# Timer_Sheet.net
KiCad netlist of a schematic drawn in Altium Designer
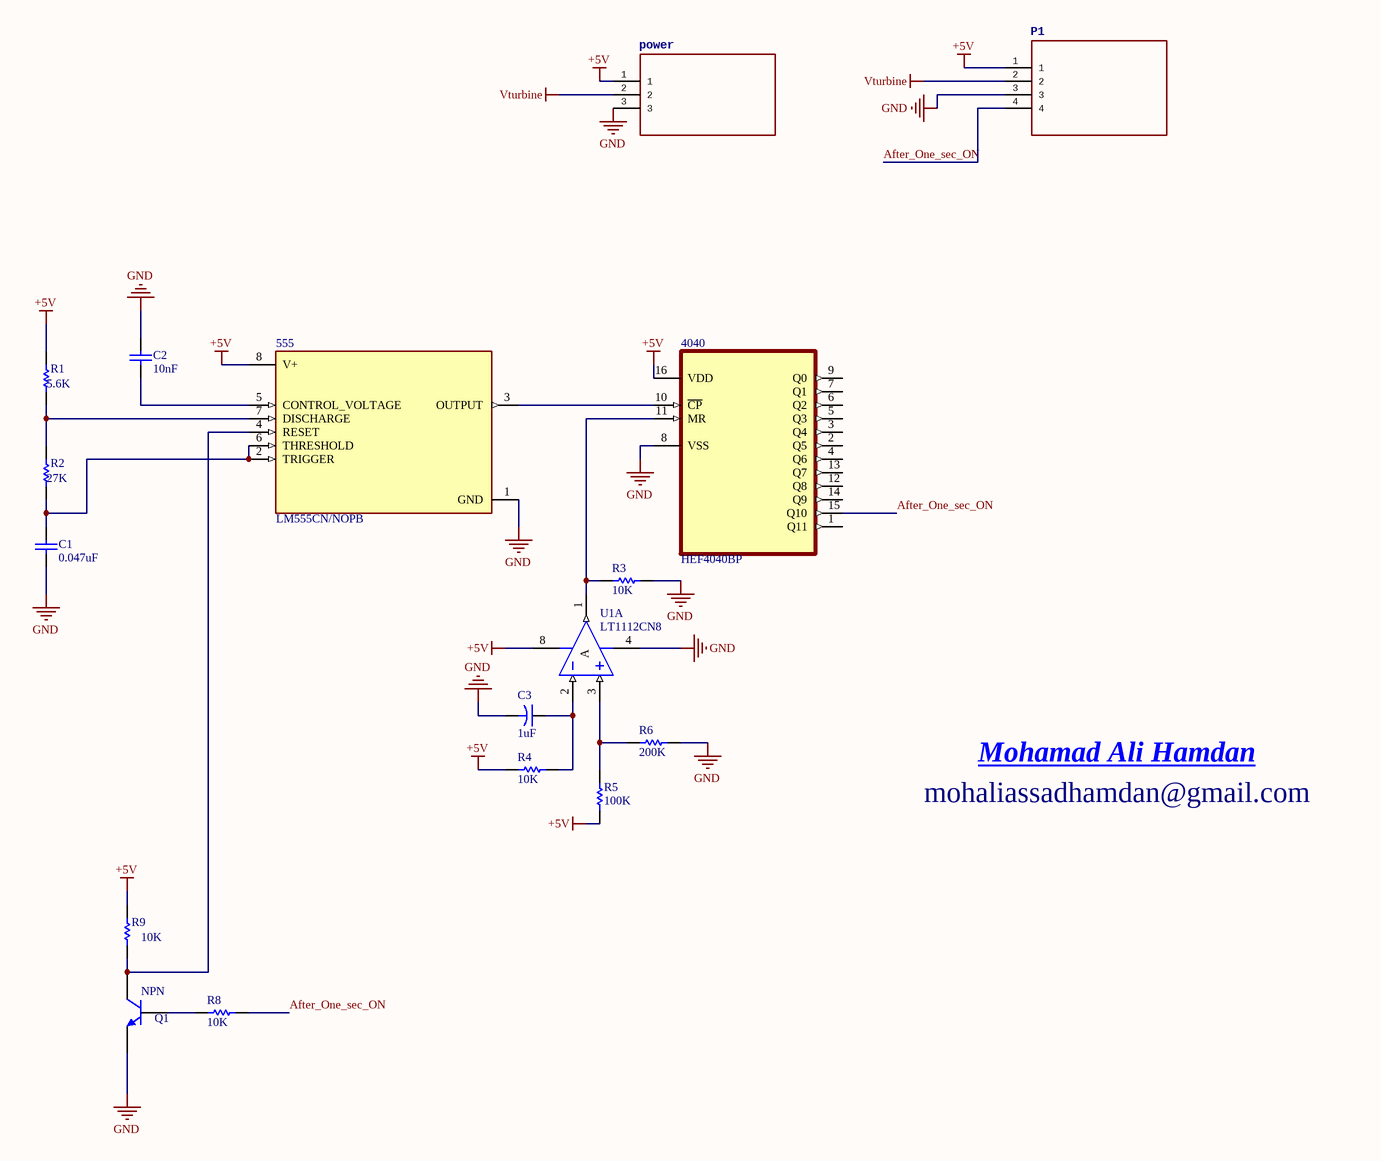
[diagram p0: Timer_Sheet.SchDoc]

(export (version "E")
  (design (tool "Eeschema 10.0.6"))
  (components
    (comp (ref "555")
      (value "LM555CN/NOPB")
      (footprint "DIP794W45P254L959H508Q8")
      (libsource (lib "LM555CN_NOPB") (part "LM555CN/NOPB"))
    )
    (comp (ref "4040")
      (value "HEF4040BP")
      (footprint "DIP254P762X420-16:DIP254P762X420-16")
      (description "Counter IC Binary Counter 1 Element 12 Bit Negative Edge 16-DIP")
      (fields (field (name "MF") "NXP USA"))
      (libsource (lib "HEF4040BP") (part "HEF4040BP"))
    )
    (comp (ref "C1")
      (value "0.047uF")
      (footprint "CAP_RDER71H333K0M1H03A")
      (description "Capacitor")
      (fields (field (name "Comment") "Cap") (field (name "PUBLISHER") "Altium Limited"))
      (libsource (lib "Miscellaneous Devices") (part "Cap"))
    )
    (comp (ref "C2")
      (value "10nF")
      (footprint "CAP_RDER71H333K0M1H03A")
      (description "Capacitor")
      (fields (field (name "Comment") "Cap") (field (name "PUBLISHER") "Altium Limited"))
      (libsource (lib "Miscellaneous Devices") (part "Cap"))
    )
    (comp (ref "C3")
      (value "1uF")
      (footprint "Capacitor_polarized_100uF")
      (description "Capacitor")
      (fields (field (name "Comment") "Cap2") (field (name "PUBLISHER") "Altium Limited"))
      (libsource (lib "Miscellaneous Devices") (part "Cap2"))
    )
    (comp (ref "P1")
      (value "SAMTEC-HTSW-104-14-X-SJ")
      (footprint "SAMTEC-HTSW-104-14-X-S")
      (libsource (lib "header_4pin_2.54mm") (part "SAMTEC-HTSW-104-14-X-SJ"))
    )
    (comp (ref "power")
      (value "SAMTEC-HTSW-103-07-X-SJ")
      (footprint "SAMTEC-HTSW-103-07-X-S")
      (libsource (lib "SAMTEC-HTSW-103-07-X-S") (part "SAMTEC-HTSW-103-07-X-SJ"))
    )
    (comp (ref "Q1")
      (value "NPN")
      (footprint "TO-226-AA")
      (description "NPN Bipolar Transistor")
      (fields (field (name "PUBLISHER") "Altium Limited"))
      (libsource (lib "Miscellaneous Devices") (part "NPN"))
    )
    (comp (ref "R1")
      (value "5.6K")
      (footprint "resistor")
      (description "Resistor")
      (fields (field (name "Comment") "Res1") (field (name "PUBLISHER") "Altium Limited"))
      (libsource (lib "Miscellaneous Devices") (part "Res1"))
    )
    (comp (ref "R2")
      (value "27K")
      (footprint "resistor")
      (description "Resistor")
      (fields (field (name "Comment") "Res1") (field (name "PUBLISHER") "Altium Limited"))
      (libsource (lib "Miscellaneous Devices") (part "Res1"))
    )
    (comp (ref "R3")
      (value "10K")
      (footprint "resistor")
      (description "Resistor")
      (fields (field (name "Comment") "Res1") (field (name "PUBLISHER") "Altium Limited"))
      (libsource (lib "Miscellaneous Devices") (part "Res1"))
    )
    (comp (ref "R4")
      (value "10K")
      (footprint "resistor")
      (description "Resistor")
      (fields (field (name "Comment") "Res1") (field (name "PUBLISHER") "Altium Limited"))
      (libsource (lib "Miscellaneous Devices") (part "Res1"))
    )
    (comp (ref "R5")
      (value "100K")
      (footprint "resistor")
      (description "Resistor")
      (fields (field (name "Comment") "Res1") (field (name "PUBLISHER") "Altium Limited"))
      (libsource (lib "Miscellaneous Devices") (part "Res1"))
    )
    (comp (ref "R6")
      (value "200K")
      (footprint "resistor")
      (description "Resistor")
      (fields (field (name "Comment") "Res1") (field (name "PUBLISHER") "Altium Limited"))
      (libsource (lib "Miscellaneous Devices") (part "Res1"))
    )
    (comp (ref "R8")
      (value "10K")
      (footprint "resistor")
      (description "Resistor")
      (fields (field (name "Comment") "Res1") (field (name "PUBLISHER") "Altium Limited"))
      (libsource (lib "Miscellaneous Devices") (part "Res1"))
    )
    (comp (ref "R9")
      (value "10K")
      (footprint "resistor")
      (description "Resistor")
      (fields (field (name "Comment") "Res1") (field (name "PUBLISHER") "Altium Limited"))
      (libsource (lib "Miscellaneous Devices") (part "Res1"))
    )
    (comp (ref "U1")
      (value "LT1112CN8")
      (footprint "DIP794W45P254L959H508Q8")
      (description "Dual Low Power Precision, Picoamp Input Operational Amplifier")
      (fields (field (name "PUBLISHER") "Altium Limited"))
      (libsource (lib "LT Operational Amplifier") (part "LT1112CN8"))
    )
  )
  (nets
    (net (code "1") (name "+5V") (class "Default")
      (node (ref "4040") (pin "16") (pinfunction "VDD_16") (pintype "power_in"))
      (node (ref "555") (pin "8") (pinfunction "V+_8") (pintype "power_in"))
      (node (ref "P1") (pin "1") (pinfunction "1_1") (pintype "passive"))
      (node (ref "R1") (pin "2") (pinfunction "2_2") (pintype "passive"))
      (node (ref "R4") (pin "1") (pinfunction "1_1") (pintype "passive"))
      (node (ref "R5") (pin "1") (pinfunction "1_1") (pintype "passive"))
      (node (ref "R9") (pin "2") (pinfunction "2_2") (pintype "passive"))
      (node (ref "U1") (pin "8") (pinfunction "V+_8") (pintype "power_in"))
      (node (ref "power") (pin "1") (pinfunction "1_1") (pintype "passive"))
    )
    (net (code "2") (name "/After_One_sec_ON") (class "Default")
      (node (ref "4040") (pin "15") (pinfunction "Q10_15") (pintype "output"))
      (node (ref "P1") (pin "4") (pinfunction "4_4") (pintype "passive"))
      (node (ref "R8") (pin "2") (pinfunction "2_2") (pintype "passive"))
    )
    (net (code "3") (name "GND") (class "Default")
      (node (ref "4040") (pin "8") (pinfunction "VSS_8") (pintype "passive"))
      (node (ref "555") (pin "1") (pinfunction "GND_1") (pintype "power_in"))
      (node (ref "C1") (pin "2") (pinfunction "2_2") (pintype "passive"))
      (node (ref "C2") (pin "1") (pinfunction "1_1") (pintype "passive"))
      (node (ref "C3") (pin "2") (pinfunction "2_2") (pintype "passive"))
      (node (ref "P1") (pin "3") (pinfunction "3_3") (pintype "passive"))
      (node (ref "Q1") (pin "3") (pinfunction "E_3") (pintype "passive"))
      (node (ref "R3") (pin "2") (pinfunction "2_2") (pintype "passive"))
      (node (ref "R6") (pin "2") (pinfunction "2_2") (pintype "passive"))
      (node (ref "U1") (pin "4") (pinfunction "V-_4") (pintype "power_in"))
      (node (ref "power") (pin "3") (pinfunction "3_3") (pintype "passive"))
    )
    (net (code "4") (name "Net-(555-CONTROL_VOLTAGE)") (class "Default")
      (node (ref "555") (pin "5") (pinfunction "CONTROL_VOLTAGE_5") (pintype "input"))
      (node (ref "C2") (pin "2") (pinfunction "2_2") (pintype "passive"))
    )
    (net (code "5") (name "Net-(555-DISCHARGE)") (class "Default")
      (node (ref "555") (pin "7") (pinfunction "DISCHARGE_7") (pintype "input"))
      (node (ref "R1") (pin "1") (pinfunction "1_1") (pintype "passive"))
      (node (ref "R2") (pin "2") (pinfunction "2_2") (pintype "passive"))
    )
    (net (code "6") (name "Net-(555-RESET)") (class "Default")
      (node (ref "555") (pin "4") (pinfunction "RESET_4") (pintype "input"))
      (node (ref "Q1") (pin "1") (pinfunction "C_1") (pintype "passive"))
      (node (ref "R9") (pin "1") (pinfunction "1_1") (pintype "passive"))
    )
    (net (code "7") (name "Net-(555-THRESHOLD)") (class "Default")
      (node (ref "555") (pin "2") (pinfunction "TRIGGER_2") (pintype "input"))
      (node (ref "555") (pin "6") (pinfunction "THRESHOLD_6") (pintype "input"))
      (node (ref "C1") (pin "1") (pinfunction "1_1") (pintype "passive"))
      (node (ref "R2") (pin "1") (pinfunction "1_1") (pintype "passive"))
    )
    (net (code "8") (name "Net-(4040-MR)") (class "Default")
      (node (ref "4040") (pin "11") (pinfunction "MR_11") (pintype "input"))
      (node (ref "R3") (pin "1") (pinfunction "1_1") (pintype "passive"))
      (node (ref "U1") (pin "1") (pinfunction "OUT_1") (pintype "output"))
    )
    (net (code "9") (name "Net-(4040-~{CP})") (class "Default")
      (node (ref "4040") (pin "10") (pinfunction "~{CP}_10") (pintype "input"))
      (node (ref "555") (pin "3") (pinfunction "OUTPUT_3") (pintype "output"))
    )
    (net (code "10") (name "Net-(Q1-B)") (class "Default")
      (node (ref "Q1") (pin "2") (pinfunction "B_2") (pintype "passive"))
      (node (ref "R8") (pin "1") (pinfunction "1_1") (pintype "passive"))
    )
    (net (code "11") (name "Net-(U1A-IN+)") (class "Default")
      (node (ref "R5") (pin "2") (pinfunction "2_2") (pintype "passive"))
      (node (ref "R6") (pin "1") (pinfunction "1_1") (pintype "passive"))
      (node (ref "U1") (pin "3") (pinfunction "IN+_3") (pintype "input"))
    )
    (net (code "12") (name "Net-(U1A-IN-)") (class "Default")
      (node (ref "C3") (pin "1") (pinfunction "1_1") (pintype "passive"))
      (node (ref "R4") (pin "2") (pinfunction "2_2") (pintype "passive"))
      (node (ref "U1") (pin "2") (pinfunction "IN-_2") (pintype "input"))
    )
    (net (code "13") (name "Vturbine") (class "Default")
      (node (ref "P1") (pin "2") (pinfunction "2_2") (pintype "passive"))
      (node (ref "power") (pin "2") (pinfunction "2_2") (pintype "passive"))
    )
    (net (code "14") (name "unconnected-(4040-Q0-Pad9)") (class "Default")
      (node (ref "4040") (pin "9") (pinfunction "Q0_9") (pintype "output"))
    )
    (net (code "15") (name "unconnected-(4040-Q1-Pad7)") (class "Default")
      (node (ref "4040") (pin "7") (pinfunction "Q1_7") (pintype "output"))
    )
    (net (code "16") (name "unconnected-(4040-Q2-Pad6)") (class "Default")
      (node (ref "4040") (pin "6") (pinfunction "Q2_6") (pintype "output"))
    )
    (net (code "17") (name "unconnected-(4040-Q3-Pad5)") (class "Default")
      (node (ref "4040") (pin "5") (pinfunction "Q3_5") (pintype "output"))
    )
    (net (code "18") (name "unconnected-(4040-Q4-Pad3)") (class "Default")
      (node (ref "4040") (pin "3") (pinfunction "Q4_3") (pintype "output"))
    )
    (net (code "19") (name "unconnected-(4040-Q5-Pad2)") (class "Default")
      (node (ref "4040") (pin "2") (pinfunction "Q5_2") (pintype "output"))
    )
    (net (code "20") (name "unconnected-(4040-Q6-Pad4)") (class "Default")
      (node (ref "4040") (pin "4") (pinfunction "Q6_4") (pintype "output"))
    )
    (net (code "21") (name "unconnected-(4040-Q7-Pad13)") (class "Default")
      (node (ref "4040") (pin "13") (pinfunction "Q7_13") (pintype "output"))
    )
    (net (code "22") (name "unconnected-(4040-Q8-Pad12)") (class "Default")
      (node (ref "4040") (pin "12") (pinfunction "Q8_12") (pintype "output"))
    )
    (net (code "23") (name "unconnected-(4040-Q9-Pad14)") (class "Default")
      (node (ref "4040") (pin "14") (pinfunction "Q9_14") (pintype "output"))
    )
    (net (code "24") (name "unconnected-(4040-Q11-Pad1)") (class "Default")
      (node (ref "4040") (pin "1") (pinfunction "Q11_1") (pintype "output"))
    )
  )
)
